# RCPYAdapter.net
KiCad netlist of a schematic drawn in EAGLE
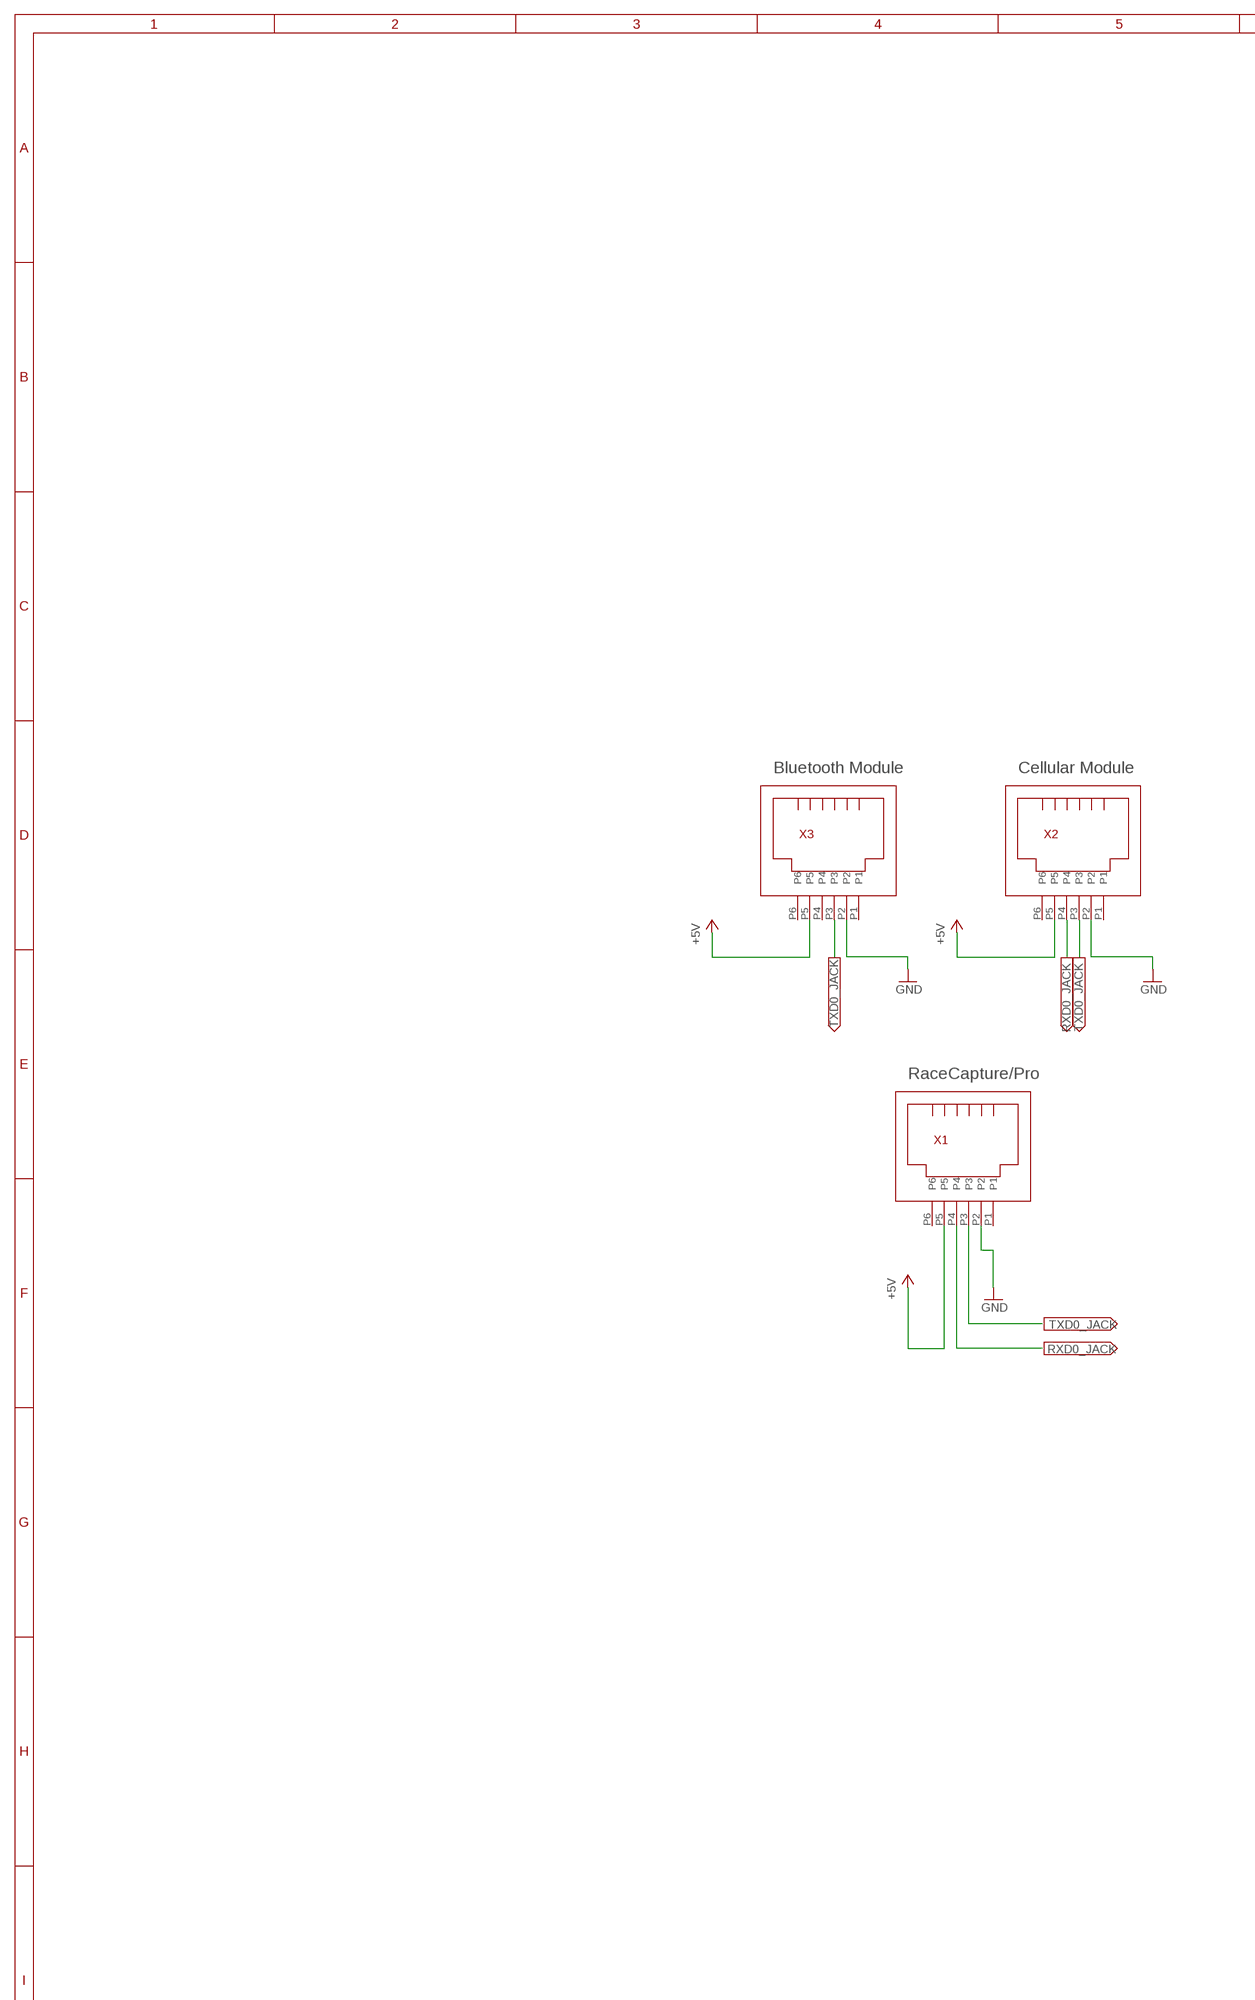
[diagram p0: schematic, sheet 1, part 1 of 2]
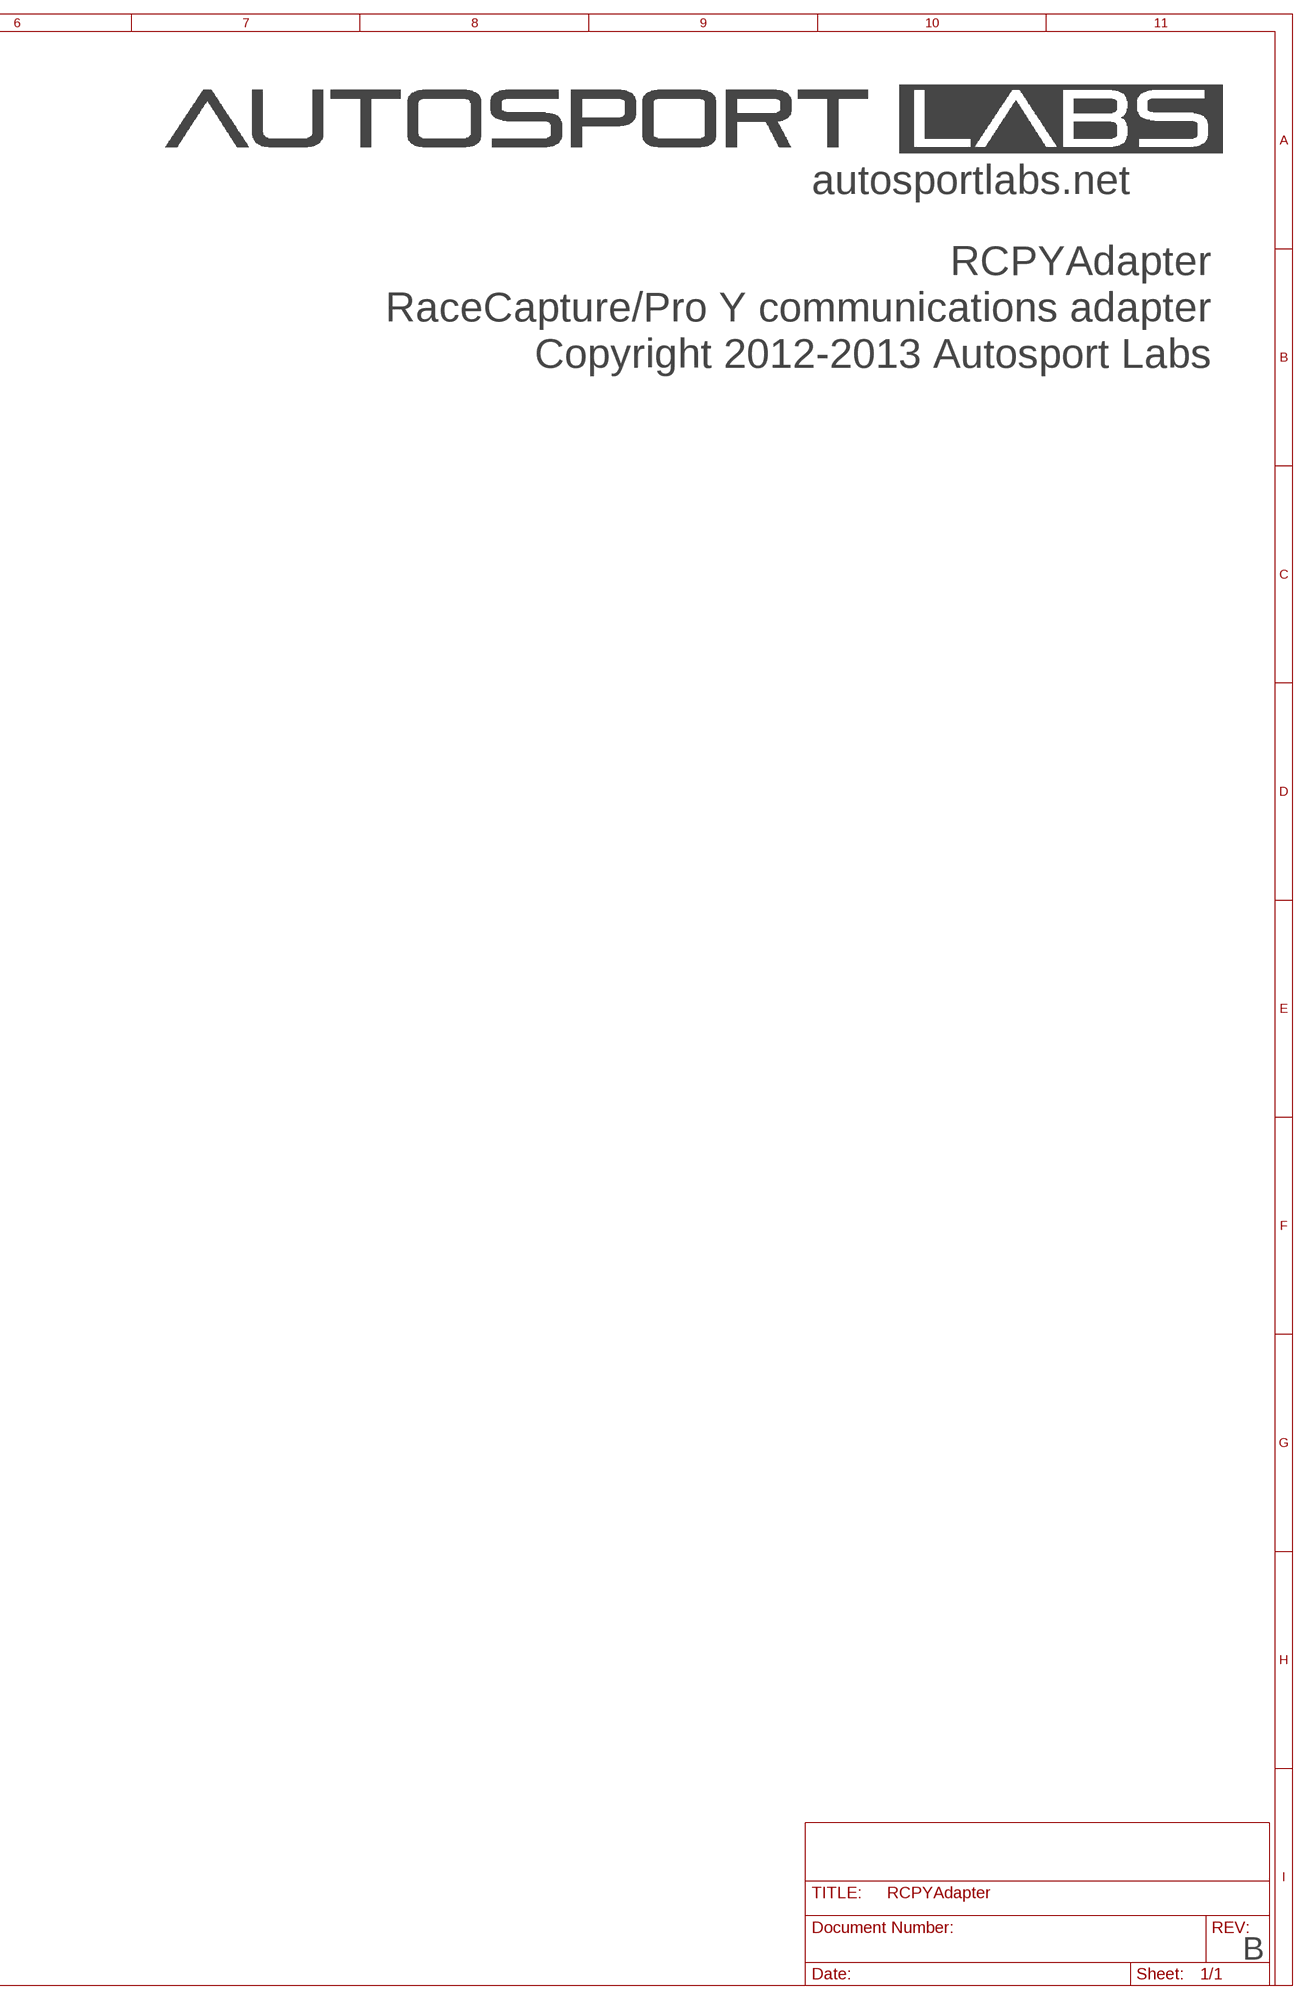
[diagram p1: schematic, sheet 1, part 2 of 2]

(export (version "E")
  (design (tool "Eeschema 10.0.6"))
  (components
    (comp (ref "X1")
      (value "FCI_88400_066LF_RJ12_4POS")
      (footprint "eagle-import:RJ12_RIGHT_ANGLE_PCB")
      (libsource (lib "eagle-import") (part "FCI_88400_066LF_RJ12_4POS"))
    )
    (comp (ref "X2")
      (value "FCI_88400_066LF_RJ12_4POS")
      (footprint "eagle-import:RJ12_RIGHT_ANGLE_PCB")
      (libsource (lib "eagle-import") (part "FCI_88400_066LF_RJ12_4POS"))
    )
    (comp (ref "X3")
      (value "FCI_88400_066LF_RJ12_4POS")
      (footprint "eagle-import:RJ12_RIGHT_ANGLE_PCB")
      (libsource (lib "eagle-import") (part "FCI_88400_066LF_RJ12_4POS"))
    )
  )
  (nets
    (net (code "1") (name "+5V") (class "Default")
      (node (ref "X1") (pin "P5") (pinfunction "P5_P5") (pintype "bidirectional"))
      (node (ref "X2") (pin "P5") (pinfunction "P5_P5") (pintype "bidirectional"))
      (node (ref "X3") (pin "P5") (pinfunction "P5_P5") (pintype "bidirectional"))
    )
    (net (code "2") (name "/RXD0_JACK") (class "Default")
      (node (ref "X1") (pin "P4") (pinfunction "P4_P4") (pintype "bidirectional"))
      (node (ref "X2") (pin "P4") (pinfunction "P4_P4") (pintype "bidirectional"))
    )
    (net (code "3") (name "/TXD0_JACK") (class "Default")
      (node (ref "X1") (pin "P3") (pinfunction "P3_P3") (pintype "bidirectional"))
      (node (ref "X2") (pin "P3") (pinfunction "P3_P3") (pintype "bidirectional"))
      (node (ref "X3") (pin "P3") (pinfunction "P3_P3") (pintype "bidirectional"))
    )
    (net (code "4") (name "GND") (class "Default")
      (node (ref "X1") (pin "P2") (pinfunction "P2_P2") (pintype "bidirectional"))
      (node (ref "X2") (pin "P2") (pinfunction "P2_P2") (pintype "bidirectional"))
      (node (ref "X3") (pin "P2") (pinfunction "P2_P2") (pintype "bidirectional"))
    )
    (net (code "5") (name "unconnected-(X1-PadP1)") (class "Default")
      (node (ref "X1") (pin "P1") (pinfunction "P1_P1") (pintype "bidirectional"))
    )
    (net (code "6") (name "unconnected-(X1-PadP6)") (class "Default")
      (node (ref "X1") (pin "P6") (pinfunction "P6_P6") (pintype "bidirectional"))
    )
    (net (code "7") (name "unconnected-(X2-PadP1)") (class "Default")
      (node (ref "X2") (pin "P1") (pinfunction "P1_P1") (pintype "bidirectional"))
    )
    (net (code "8") (name "unconnected-(X2-PadP6)") (class "Default")
      (node (ref "X2") (pin "P6") (pinfunction "P6_P6") (pintype "bidirectional"))
    )
    (net (code "9") (name "unconnected-(X3-PadP1)") (class "Default")
      (node (ref "X3") (pin "P1") (pinfunction "P1_P1") (pintype "bidirectional"))
    )
    (net (code "10") (name "unconnected-(X3-PadP4)") (class "Default")
      (node (ref "X3") (pin "P4") (pinfunction "P4_P4") (pintype "bidirectional"))
    )
    (net (code "11") (name "unconnected-(X3-PadP6)") (class "Default")
      (node (ref "X3") (pin "P6") (pinfunction "P6_P6") (pintype "bidirectional"))
    )
  )
)
